# MODISLIM.net
KiCad netlist of a schematic drawn in EAGLE
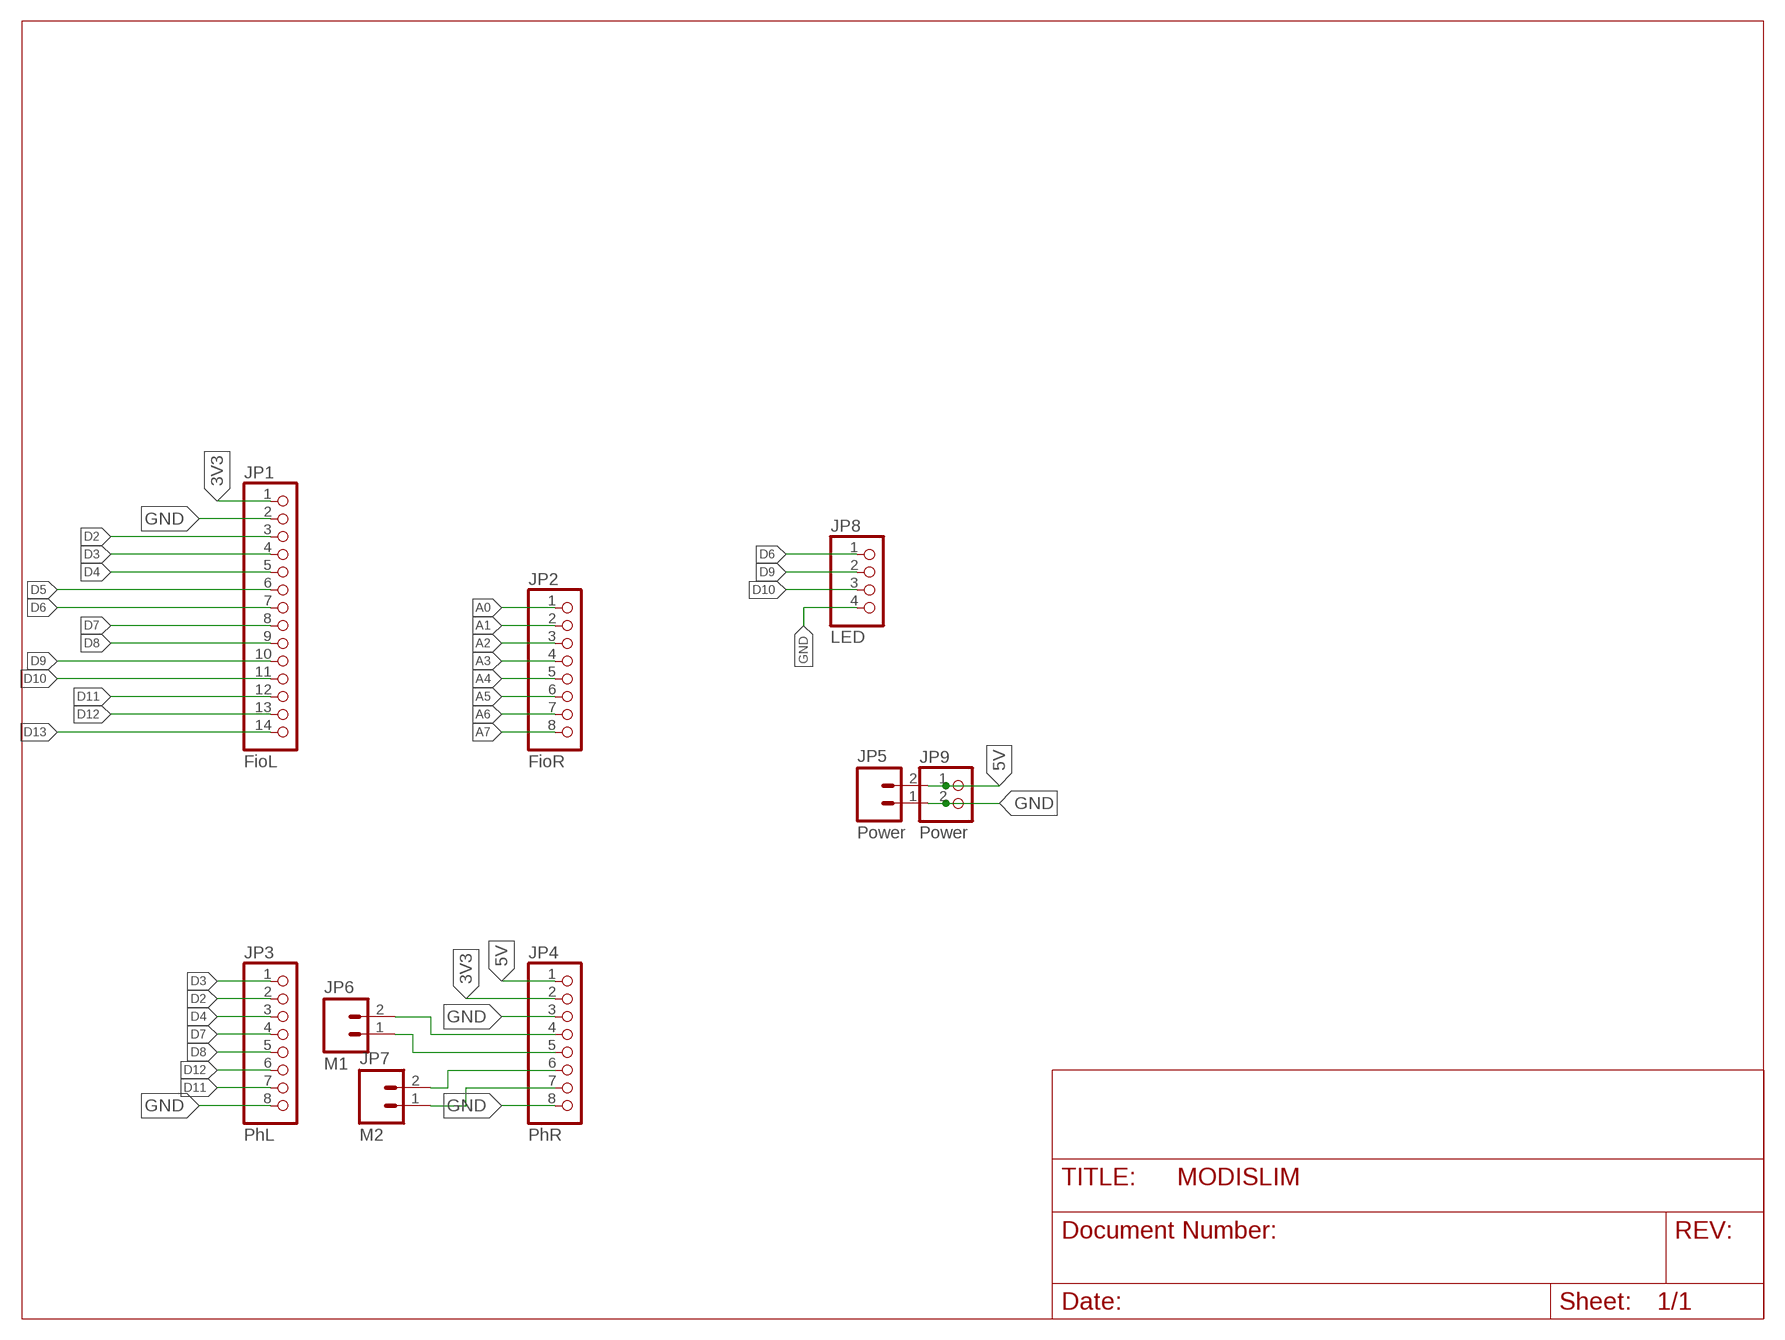
[diagram p0: schematic, sheet 1]

(export (version "E")
  (design (tool "Eeschema 10.0.6"))
  (components
    (comp (ref "JP1")
      (value "FioL")
      (footprint "eagle-import:1X14")
      (libsource (lib "eagle-import") (part "PINHD-1X14"))
    )
    (comp (ref "JP2")
      (value "FioR")
      (footprint "eagle-import:1X08")
      (libsource (lib "eagle-import") (part "PINHD-1X8"))
    )
    (comp (ref "JP3")
      (value "PhL")
      (footprint "eagle-import:1X08")
      (libsource (lib "eagle-import") (part "PINHD-1X8"))
    )
    (comp (ref "JP4")
      (value "PhR")
      (footprint "eagle-import:1X08")
      (libsource (lib "eagle-import") (part "PINHD-1X8"))
    )
    (comp (ref "JP5")
      (value "Power")
      (footprint "eagle-import:SCREWTERMINAL-3.5MM-2")
      (libsource (lib "eagle-import") (part "M023.5MM"))
    )
    (comp (ref "JP6")
      (value "M1")
      (footprint "eagle-import:SCREWTERMINAL-3.5MM-2")
      (libsource (lib "eagle-import") (part "M023.5MM"))
    )
    (comp (ref "JP7")
      (value "M2")
      (footprint "eagle-import:SCREWTERMINAL-3.5MM-2")
      (libsource (lib "eagle-import") (part "M023.5MM"))
    )
    (comp (ref "JP8")
      (value "LED")
      (footprint "eagle-import:1X04")
      (libsource (lib "eagle-import") (part "PINHD-1X4"))
    )
    (comp (ref "JP9")
      (value "Power")
      (footprint "eagle-import:1X02")
      (libsource (lib "eagle-import") (part "PINHD-1X2"))
    )
  )
  (nets
    (net (code "1") (name "3V3") (class "Default")
      (node (ref "JP1") (pin "1") (pinfunction "1_1") (pintype "passive"))
      (node (ref "JP4") (pin "2") (pinfunction "2_2") (pintype "passive"))
    )
    (net (code "2") (name "5V") (class "Default")
      (node (ref "JP4") (pin "1") (pinfunction "1_1") (pintype "passive"))
      (node (ref "JP5") (pin "2") (pinfunction "2_2") (pintype "passive"))
      (node (ref "JP9") (pin "1") (pinfunction "1_1") (pintype "passive"))
    )
    (net (code "3") (name "A0") (class "Default")
      (node (ref "JP2") (pin "1") (pinfunction "1_1") (pintype "passive"))
    )
    (net (code "4") (name "A1") (class "Default")
      (node (ref "JP2") (pin "2") (pinfunction "2_2") (pintype "passive"))
    )
    (net (code "5") (name "A2") (class "Default")
      (node (ref "JP2") (pin "3") (pinfunction "3_3") (pintype "passive"))
    )
    (net (code "6") (name "A3") (class "Default")
      (node (ref "JP2") (pin "4") (pinfunction "4_4") (pintype "passive"))
    )
    (net (code "7") (name "A4") (class "Default")
      (node (ref "JP2") (pin "5") (pinfunction "5_5") (pintype "passive"))
    )
    (net (code "8") (name "A5") (class "Default")
      (node (ref "JP2") (pin "6") (pinfunction "6_6") (pintype "passive"))
    )
    (net (code "9") (name "A6") (class "Default")
      (node (ref "JP2") (pin "7") (pinfunction "7_7") (pintype "passive"))
    )
    (net (code "10") (name "A7") (class "Default")
      (node (ref "JP2") (pin "8") (pinfunction "8_8") (pintype "passive"))
    )
    (net (code "11") (name "D2") (class "Default")
      (node (ref "JP1") (pin "3") (pinfunction "3_3") (pintype "passive"))
      (node (ref "JP3") (pin "2") (pinfunction "2_2") (pintype "passive"))
    )
    (net (code "12") (name "D3") (class "Default")
      (node (ref "JP1") (pin "4") (pinfunction "4_4") (pintype "passive"))
      (node (ref "JP3") (pin "1") (pinfunction "1_1") (pintype "passive"))
    )
    (net (code "13") (name "D4") (class "Default")
      (node (ref "JP1") (pin "5") (pinfunction "5_5") (pintype "passive"))
      (node (ref "JP3") (pin "3") (pinfunction "3_3") (pintype "passive"))
    )
    (net (code "14") (name "D5") (class "Default")
      (node (ref "JP1") (pin "6") (pinfunction "6_6") (pintype "passive"))
    )
    (net (code "15") (name "D6") (class "Default")
      (node (ref "JP1") (pin "7") (pinfunction "7_7") (pintype "passive"))
      (node (ref "JP8") (pin "1") (pinfunction "1_1") (pintype "passive"))
    )
    (net (code "16") (name "D7") (class "Default")
      (node (ref "JP1") (pin "8") (pinfunction "8_8") (pintype "passive"))
      (node (ref "JP3") (pin "4") (pinfunction "4_4") (pintype "passive"))
    )
    (net (code "17") (name "D8") (class "Default")
      (node (ref "JP1") (pin "9") (pinfunction "9_9") (pintype "passive"))
      (node (ref "JP3") (pin "5") (pinfunction "5_5") (pintype "passive"))
    )
    (net (code "18") (name "D9") (class "Default")
      (node (ref "JP1") (pin "10") (pinfunction "10_10") (pintype "passive"))
      (node (ref "JP8") (pin "2") (pinfunction "2_2") (pintype "passive"))
    )
    (net (code "19") (name "D10") (class "Default")
      (node (ref "JP1") (pin "11") (pinfunction "11_11") (pintype "passive"))
      (node (ref "JP8") (pin "3") (pinfunction "3_3") (pintype "passive"))
    )
    (net (code "20") (name "D11") (class "Default")
      (node (ref "JP1") (pin "12") (pinfunction "12_12") (pintype "passive"))
      (node (ref "JP3") (pin "7") (pinfunction "7_7") (pintype "passive"))
    )
    (net (code "21") (name "D12") (class "Default")
      (node (ref "JP1") (pin "13") (pinfunction "13_13") (pintype "passive"))
      (node (ref "JP3") (pin "6") (pinfunction "6_6") (pintype "passive"))
    )
    (net (code "22") (name "D13") (class "Default")
      (node (ref "JP1") (pin "14") (pinfunction "14_14") (pintype "passive"))
    )
    (net (code "23") (name "GND") (class "Default")
      (node (ref "JP1") (pin "2") (pinfunction "2_2") (pintype "passive"))
      (node (ref "JP3") (pin "8") (pinfunction "8_8") (pintype "passive"))
      (node (ref "JP4") (pin "3") (pinfunction "3_3") (pintype "passive"))
      (node (ref "JP4") (pin "8") (pinfunction "8_8") (pintype "passive"))
      (node (ref "JP5") (pin "1") (pinfunction "1_1") (pintype "passive"))
      (node (ref "JP8") (pin "4") (pinfunction "4_4") (pintype "passive"))
      (node (ref "JP9") (pin "2") (pinfunction "2_2") (pintype "passive"))
    )
    (net (code "24") (name "Net-(JP4-Pad4)") (class "Default")
      (node (ref "JP4") (pin "4") (pinfunction "4_4") (pintype "passive"))
      (node (ref "JP6") (pin "2") (pinfunction "2_2") (pintype "passive"))
    )
    (net (code "25") (name "Net-(JP4-Pad5)") (class "Default")
      (node (ref "JP4") (pin "5") (pinfunction "5_5") (pintype "passive"))
      (node (ref "JP6") (pin "1") (pinfunction "1_1") (pintype "passive"))
    )
    (net (code "26") (name "Net-(JP4-Pad6)") (class "Default")
      (node (ref "JP4") (pin "6") (pinfunction "6_6") (pintype "passive"))
      (node (ref "JP7") (pin "2") (pinfunction "2_2") (pintype "passive"))
    )
    (net (code "27") (name "Net-(JP4-Pad7)") (class "Default")
      (node (ref "JP4") (pin "7") (pinfunction "7_7") (pintype "passive"))
      (node (ref "JP7") (pin "1") (pinfunction "1_1") (pintype "passive"))
    )
  )
)
